# Protection_Circuit_5V.net
KiCad netlist of a schematic drawn in Altium Designer
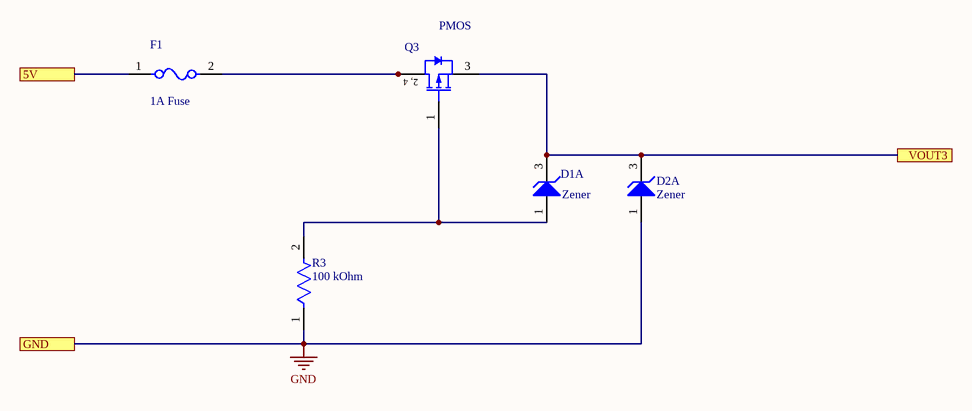
[diagram p0: Protection Circuit 5V.SchDoc]

(export (version "E")
  (design (tool "Eeschema 10.0.6"))
  (components
    (comp (ref "D1")
      (value "Zener")
      (footprint "ONSC-SOT-23-3-318-08_V")
      (description "Zener Voltage Regulator, 225 mW, 3-Pin SOT-23, Pb-Free, Tape and Reel")
      (fields (field (name "PARTNUMBER") "MMBZ5245BLT3G") (field (name "MANUFACTURER") "On Semiconductor"))
      (libsource (lib "Altium Content Vault") (part "ONSC-A1K3-3"))
    )
    (comp (ref "D2")
      (value "Zener")
      (footprint "ONSC-SOT-23-3-318-08_V")
      (description "Zener Voltage Regulator, 225 mW, 3-Pin SOT-23, Pb-Free, Tape and Reel")
      (fields (field (name "PARTNUMBER") "SZBZX84C39ET1G") (field (name "MANUFACTURER") "On Semiconductor"))
      (libsource (lib "Altium Content Vault") (part "ONSC-A1K3-3"))
    )
    (comp (ref "F1")
      (value "1A Fuse")
      (footprint "FP-0603SFS-MFG")
      (description "FUSE BOARD MOUNT 1A 32VDC 0603")
      (fields
        (field (name "OCTOPART") "https://octopart.com/0603sfs100f%2F32-2-littelfuse-74214378")
        (field (name "MANUFACTURER PART NUMBER") "0603SFS100F/32-2")
      )
      (libsource (lib "Altium Content Vault") (part "5bcf9b9f640e542cf0359d10258e979"))
    )
    (comp (ref "Q3")
      (value "PMOS")
      (footprint "FAIR-SOT223-4_V")
      (fields (field (name "MANUFACTURER") "Fairchild Semiconductor"))
      (libsource (lib "Altium Content Vault") (part "PEMOS-GDSD-4"))
    )
    (comp (ref "R3")
      (value "100 kOhm")
      (footprint "FP-CR0805-MFG")
      (description "Thick Film Chip Resistors 0805 100kΩ 0.125W 5% 200ppm/°C")
      (fields (field (name "TOLERANCE") "5%"))
      (libsource (lib "Altium Content Vault") (part "1029c3af85768c4190bb7ad29bc67b5"))
    )
  )
  (nets
    (net (code "1") (name "/5V") (class "Default")
      (node (ref "F1") (pin "1") (pinfunction "1_1") (pintype "passive"))
    )
    (net (code "2") (name "/VOUT3") (class "Default")
      (node (ref "D1") (pin "3") (pinfunction "K_3") (pintype "passive"))
      (node (ref "D2") (pin "3") (pinfunction "K_3") (pintype "passive"))
      (node (ref "Q3") (pin "3") (pinfunction "SOURCE_3") (pintype "passive"))
    )
    (net (code "3") (name "GND") (class "Default")
      (node (ref "D2") (pin "1") (pinfunction "A_1") (pintype "passive"))
      (node (ref "R3") (pin "1") (pinfunction "1_1") (pintype "passive"))
    )
    (net (code "4") (name "Net-(D1A-A)") (class "Default")
      (node (ref "D1") (pin "1") (pinfunction "A_1") (pintype "passive"))
      (node (ref "Q3") (pin "1") (pinfunction "GATE_1") (pintype "passive"))
      (node (ref "R3") (pin "2") (pinfunction "2_2") (pintype "passive"))
    )
    (net (code "5") (name "Net-(F1-Pad2)") (class "Default")
      (node (ref "F1") (pin "2") (pinfunction "2_2") (pintype "passive"))
      (node (ref "Q3") (pin "2") (pinfunction "DRAIN_2") (pintype "passive"))
      (node (ref "Q3") (pin "4") (pinfunction "DRAIN_4") (pintype "passive"))
    )
  )
)
